# LCD.net
KiCad netlist of a schematic drawn in Altium Designer
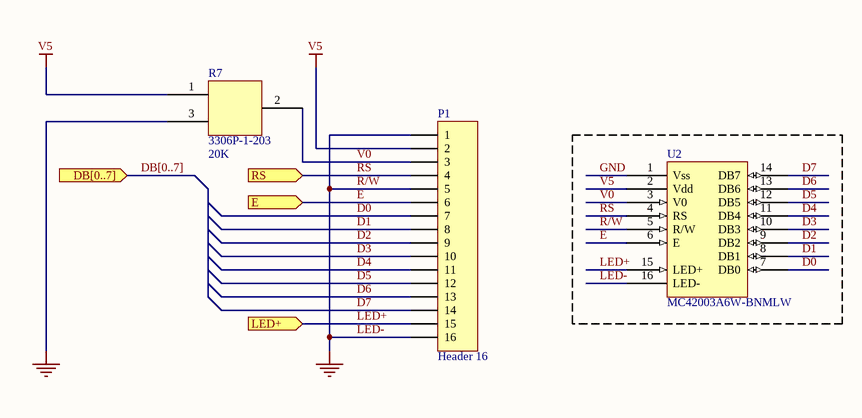
[diagram p0: LCD.SchDoc]

(export (version "E")
  (design (tool "Eeschema 10.0.6"))
  (components
    (comp (ref "P1")
      (value "Header 16")
      (footprint "MC42004A6W-BNMLW")
      (description "Header, 16-Pin")
      (libsource (lib "Miscellaneous Connectors") (part "Header 16"))
    )
    (comp (ref "R7")
      (value "3306P-1-203")
      (footprint "3306P-1-202")
      (description "Trimpot")
      (fields (field (name "ALTIUM_VALUE") "20K"))
      (libsource (lib "Components") (part "3306P-1-202"))
    )
    (comp (ref "U2")
      (value "MC42003A6W-BNMLW")
      (footprint "MC42004A6W-BNMLW")
      (description "LCD")
      (libsource (lib "Components") (part "MC42003A6W-BNMLW"))
    )
  )
  (nets
    (net (code "9") (name "/D0") (class "Default")
      (node (ref "P1") (pin "7") (pinfunction "7_7") (pintype "passive"))
      (node (ref "U2") (pin "7") (pinfunction "DB0_7") (pintype "bidirectional"))
    )
    (net (code "10") (name "/D1") (class "Default")
      (node (ref "P1") (pin "8") (pinfunction "8_8") (pintype "passive"))
      (node (ref "U2") (pin "8") (pinfunction "DB1_8") (pintype "bidirectional"))
    )
    (net (code "11") (name "/D2") (class "Default")
      (node (ref "P1") (pin "9") (pinfunction "9_9") (pintype "passive"))
      (node (ref "U2") (pin "9") (pinfunction "DB2_9") (pintype "bidirectional"))
    )
    (net (code "12") (name "/D3") (class "Default")
      (node (ref "P1") (pin "10") (pinfunction "10_10") (pintype "passive"))
      (node (ref "U2") (pin "10") (pinfunction "DB3_10") (pintype "bidirectional"))
    )
    (net (code "13") (name "/D4") (class "Default")
      (node (ref "P1") (pin "11") (pinfunction "11_11") (pintype "passive"))
      (node (ref "U2") (pin "11") (pinfunction "DB4_11") (pintype "bidirectional"))
    )
    (net (code "14") (name "/D5") (class "Default")
      (node (ref "P1") (pin "12") (pinfunction "12_12") (pintype "passive"))
      (node (ref "U2") (pin "12") (pinfunction "DB5_12") (pintype "bidirectional"))
    )
    (net (code "15") (name "/D6") (class "Default")
      (node (ref "P1") (pin "13") (pinfunction "13_13") (pintype "passive"))
      (node (ref "U2") (pin "13") (pinfunction "DB6_13") (pintype "bidirectional"))
    )
    (net (code "16") (name "/D7") (class "Default")
      (node (ref "P1") (pin "14") (pinfunction "14_14") (pintype "passive"))
      (node (ref "U2") (pin "14") (pinfunction "DB7_14") (pintype "bidirectional"))
    )
    (net (code "18") (name "/E") (class "Default")
      (node (ref "P1") (pin "6") (pinfunction "6_6") (pintype "passive"))
      (node (ref "U2") (pin "6") (pinfunction "E_6") (pintype "input"))
    )
    (net (code "19") (name "/LED+") (class "Default")
      (node (ref "P1") (pin "15") (pinfunction "15_15") (pintype "passive"))
      (node (ref "U2") (pin "15") (pinfunction "LED+_15") (pintype "input"))
    )
    (net (code "20") (name "/RS") (class "Default")
      (node (ref "P1") (pin "4") (pinfunction "4_4") (pintype "passive"))
      (node (ref "U2") (pin "4") (pinfunction "RS_4") (pintype "input"))
    )
    (net (code "21") (name "/V0") (class "Default")
      (node (ref "P1") (pin "3") (pinfunction "3_3") (pintype "passive"))
      (node (ref "R7") (pin "2") (pinfunction "2_2") (pintype "power_in"))
      (node (ref "U2") (pin "3") (pinfunction "V0_3") (pintype "input"))
    )
    (net (code "22") (name "GND") (class "Default")
      (node (ref "P1") (pin "1") (pinfunction "1_1") (pintype "passive"))
      (node (ref "P1") (pin "16") (pinfunction "16_16") (pintype "passive"))
      (node (ref "P1") (pin "5") (pinfunction "5_5") (pintype "passive"))
      (node (ref "R7") (pin "3") (pinfunction "3_3") (pintype "power_in"))
      (node (ref "U2") (pin "1") (pinfunction "Vss_1") (pintype "power_in"))
      (node (ref "U2") (pin "16") (pinfunction "LED-_16") (pintype "power_in"))
      (node (ref "U2") (pin "5") (pinfunction "R/W_5") (pintype "input"))
    )
    (net (code "23") (name "V5") (class "Default")
      (node (ref "P1") (pin "2") (pinfunction "2_2") (pintype "passive"))
      (node (ref "R7") (pin "1") (pinfunction "1_1") (pintype "power_in"))
      (node (ref "U2") (pin "2") (pinfunction "Vdd_2") (pintype "power_in"))
    )
  )
)
